# SparkX_smol_Power_AAA.net
KiCad netlist of a schematic drawn in EAGLE
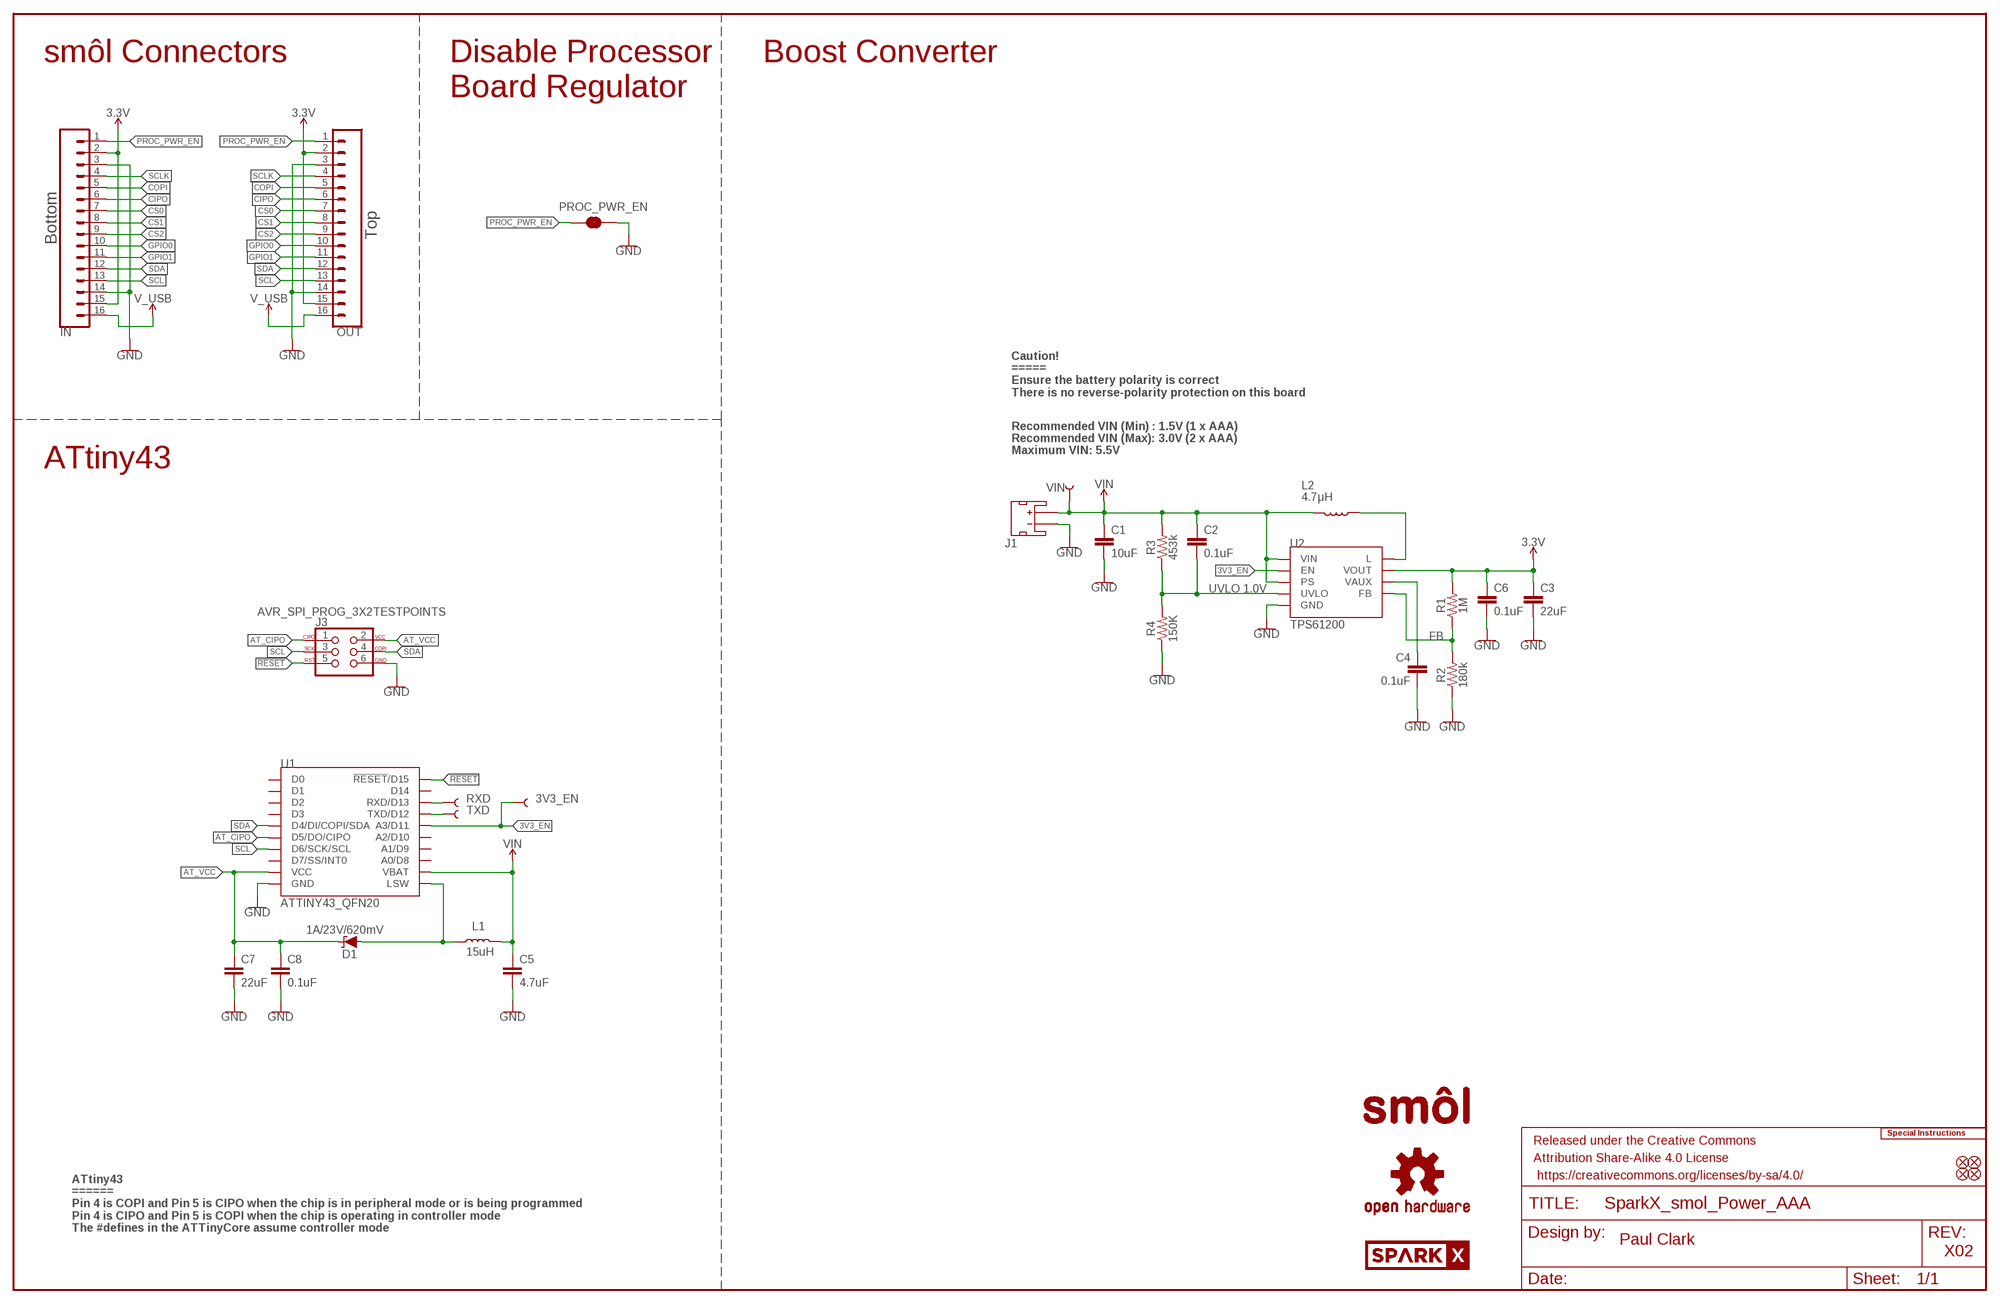
[diagram p0: schematic, sheet 1]

(export (version "E")
  (design (tool "Eeschema 10.0.6"))
  (components
    (comp (ref "3V3_EN")
      (value "TEST-POINT3X4")
      (footprint "eagle-import:PAD.03X.04")
      (libsource (lib "eagle-import") (part "TEST-POINT3X4"))
    )
    (comp (ref "C1")
      (value "10uF")
      (footprint "eagle-import:0402-TIGHT")
      (libsource (lib "eagle-import") (part "10UF-0402T-6.3V-20%"))
    )
    (comp (ref "C2")
      (value "0.1uF")
      (footprint "eagle-import:0402-TIGHT")
      (libsource (lib "eagle-import") (part "0.1UF-0402T-6.3V-10%-X7R"))
    )
    (comp (ref "C3")
      (value "22uF")
      (footprint "eagle-import:0603")
      (libsource (lib "eagle-import") (part "22UF-0603-6.3V-20%"))
    )
    (comp (ref "C4")
      (value "0.1uF")
      (footprint "eagle-import:0402-TIGHT")
      (libsource (lib "eagle-import") (part "0.1UF-0402T-6.3V-10%-X7R"))
    )
    (comp (ref "C5")
      (value "4.7uF")
      (footprint "eagle-import:0402-TIGHT")
      (libsource (lib "eagle-import") (part "4.7UF-0402_TIGHT-6.3V-20%-X5R"))
    )
    (comp (ref "C6")
      (value "0.1uF")
      (footprint "eagle-import:0402-TIGHT")
      (libsource (lib "eagle-import") (part "0.1UF-0402T-6.3V-10%-X7R"))
    )
    (comp (ref "C7")
      (value "22uF")
      (footprint "eagle-import:0603")
      (libsource (lib "eagle-import") (part "22UF-0603-6.3V-20%"))
    )
    (comp (ref "C8")
      (value "0.1uF")
      (footprint "eagle-import:0402-TIGHT")
      (libsource (lib "eagle-import") (part "0.1UF-0402T-6.3V-10%-X7R"))
    )
    (comp (ref "D1")
      (value "1A/23V/620mV")
      (footprint "eagle-import:SOD-323")
      (libsource (lib "eagle-import") (part "DIODE-SCHOTTKY-BAT20J"))
    )
    (comp (ref "FD1")
      (value "FIDUCIALUFIDUCIAL")
      (footprint "eagle-import:FIDUCIAL-MICRO")
      (libsource (lib "eagle-import") (part "FIDUCIALUFIDUCIAL"))
    )
    (comp (ref "FD2")
      (value "FIDUCIALUFIDUCIAL")
      (footprint "eagle-import:FIDUCIAL-MICRO")
      (libsource (lib "eagle-import") (part "FIDUCIALUFIDUCIAL"))
    )
    (comp (ref "FD3")
      (value "FIDUCIALUFIDUCIAL")
      (footprint "eagle-import:FIDUCIAL-MICRO")
      (libsource (lib "eagle-import") (part "FIDUCIALUFIDUCIAL"))
    )
    (comp (ref "FD4")
      (value "FIDUCIALUFIDUCIAL")
      (footprint "eagle-import:FIDUCIAL-MICRO")
      (libsource (lib "eagle-import") (part "FIDUCIALUFIDUCIAL"))
    )
    (comp (ref "FRAME1")
      (value "FRAME-LEDGER")
      (footprint "eagle-import:CREATIVE_COMMONS")
      (libsource (lib "eagle-import") (part "FRAME-LEDGER"))
    )
    (comp (ref "IN")
      (value "CONN_16FPC_16_0.5MM")
      (footprint "eagle-import:FPC_16_0.5MM")
      (libsource (lib "eagle-import") (part "CONN_16FPC_16_0.5MM"))
    )
    (comp (ref "J1")
      (value "JST_2MM_MALE")
      (footprint "eagle-import:JST-2-SMD")
      (libsource (lib "eagle-import") (part "JST_2MM_MALE"))
    )
    (comp (ref "J3")
      (value "AVR_SPI_PROG_3X2TESTPOINTS")
      (footprint "eagle-import:2X3_TEST_POINTS")
      (libsource (lib "eagle-import") (part "AVR_SPI_PROG_3X2TESTPOINTS"))
    )
    (comp (ref "L1")
      (value "15uH")
      (footprint "eagle-import:INDUCTOR_LQH32")
      (libsource (lib "eagle-import") (part "INDUCTOR-LHQ32-15UH"))
    )
    (comp (ref "L2")
      (value "4.7μH")
      (footprint "eagle-import:INDUCTOR_4X4MM")
      (libsource (lib "eagle-import") (part "4.7μH_SHIELDED_INDUCTORNPIS_LS"))
    )
    (comp (ref "LOGO1")
      (value "SPECIAL_INSTRUCTIONS-ORDERING")
      (footprint "eagle-import:ORDERING_INSTRUCTIONS")
      (libsource (lib "eagle-import") (part "SPECIAL_INSTRUCTIONS-ORDERING"))
    )
    (comp (ref "LOGO2")
      (value "OSHW-LOGOMINI")
      (footprint "eagle-import:OSHW-LOGO-MINI")
      (libsource (lib "eagle-import") (part "OSHW-LOGOMINI"))
    )
    (comp (ref "LOGO3")
      (value "OSHW-LOGOMINI")
      (footprint "eagle-import:OSHW-LOGO-MINI")
      (libsource (lib "eagle-import") (part "OSHW-LOGOMINI"))
    )
    (comp (ref "OUT")
      (value "CONN_16FPC_16_0.5MM")
      (footprint "eagle-import:FPC_16_0.5MM")
      (libsource (lib "eagle-import") (part "CONN_16FPC_16_0.5MM"))
    )
    (comp (ref "PROC_PWR_EN")
      (value "JUMPER-SMT_2_NC_TRACE_SILK")
      (footprint "eagle-import:SMT-JUMPER_2_NC_TRACE_SILK")
      (libsource (lib "eagle-import") (part "JUMPER-SMT_2_NC_TRACE_SILK"))
    )
    (comp (ref "R1")
      (value "1M")
      (footprint "eagle-import:0402-TIGHT")
      (libsource (lib "eagle-import") (part "1MOHM-0402T-1/16W-5%"))
    )
    (comp (ref "R2")
      (value "180k")
      (footprint "eagle-import:0402-TIGHT")
      (libsource (lib "eagle-import") (part "180KOHM-0402T-1/16W-1%"))
    )
    (comp (ref "R3")
      (value "453k")
      (footprint "eagle-import:0402-TIGHT")
      (libsource (lib "eagle-import") (part "453KOHM-0402T-1/16W-1%"))
    )
    (comp (ref "R4")
      (value "150K")
      (footprint "eagle-import:0402-TIGHT")
      (libsource (lib "eagle-import") (part "150KOHM-0402T-1/16W-1%"))
    )
    (comp (ref "RXD")
      (value "TEST-POINT3X4")
      (footprint "eagle-import:PAD.03X.04")
      (libsource (lib "eagle-import") (part "TEST-POINT3X4"))
    )
    (comp (ref "TXD")
      (value "TEST-POINT3X4")
      (footprint "eagle-import:PAD.03X.04")
      (libsource (lib "eagle-import") (part "TEST-POINT3X4"))
    )
    (comp (ref "U$1")
      (value "SPARKX-LOGO3")
      (footprint "eagle-import:SPARKX-SMALL")
      (libsource (lib "eagle-import") (part "SPARKX-LOGO3"))
    )
    (comp (ref "U$13")
      (value "SMOL_LOGOSMALL")
      (footprint "eagle-import:SMOL_SMALL")
      (libsource (lib "eagle-import") (part "SMOL_LOGOSMALL"))
    )
    (comp (ref "U$14")
      (value "SMOL_LOGOSMALL")
      (footprint "eagle-import:SMOL_SMALL")
      (libsource (lib "eagle-import") (part "SMOL_LOGOSMALL"))
    )
    (comp (ref "U1")
      (value "ATTINY43_QFN20")
      (footprint "eagle-import:QFN20_20M1")
      (fields (field (name "DIGIKEY_PART") "ATTINY43U-MU-ND") (field (name "MANU_PART") "ATtiny43U-MU"))
      (libsource (lib "eagle-import") (part "ATTINY43_QFN20"))
    )
    (comp (ref "U2")
      (value "TPS61200")
      (footprint "eagle-import:QFN-10_PAD")
      (libsource (lib "eagle-import") (part "TPS61200_MINIMAL"))
    )
    (comp (ref "VIN")
      (value "TEST-POINT3X4")
      (footprint "eagle-import:PAD.03X.04")
      (libsource (lib "eagle-import") (part "TEST-POINT3X4"))
    )
  )
  (nets
    (net (code "1") (name "/FB") (class "Default")
      (node (ref "R1") (pin "1") (pinfunction "1_1") (pintype "passive"))
      (node (ref "R2") (pin "2") (pinfunction "2_2") (pintype "passive"))
      (node (ref "U2") (pin "10") (pinfunction "FB_10") (pintype "passive"))
    )
    (net (code "2") (name "/~{RESET}") (class "Default")
      (node (ref "J3") (pin "5") (pinfunction "5_5") (pintype "passive"))
      (node (ref "U1") (pin "18") (pinfunction "~{RESET}/D15_18") (pintype "bidirectional"))
    )
    (net (code "3") (name "3.3V") (class "Default")
      (node (ref "C3") (pin "1") (pinfunction "1_1") (pintype "passive"))
      (node (ref "C6") (pin "1") (pinfunction "1_1") (pintype "passive"))
      (node (ref "IN") (pin "15") (pinfunction "15_15") (pintype "passive"))
      (node (ref "IN") (pin "2") (pinfunction "2_2") (pintype "passive"))
      (node (ref "OUT") (pin "15") (pinfunction "15_15") (pintype "passive"))
      (node (ref "OUT") (pin "2") (pinfunction "2_2") (pintype "passive"))
      (node (ref "R1") (pin "2") (pinfunction "2_2") (pintype "passive"))
      (node (ref "U2") (pin "2") (pinfunction "VOUT_2") (pintype "power_in"))
    )
    (net (code "4") (name "3V3_EN") (class "Default")
      (node (ref "3V3_EN") (pin "1") (pinfunction "1_1") (pintype "bidirectional"))
      (node (ref "U1") (pin "14") (pinfunction "A3/D11_14") (pintype "bidirectional"))
      (node (ref "U2") (pin "6") (pinfunction "EN_6") (pintype "input"))
    )
    (net (code "5") (name "AT_CIPO") (class "Default")
      (node (ref "J3") (pin "1") (pinfunction "1_1") (pintype "passive"))
      (node (ref "U1") (pin "4") (pinfunction "D5/DO/CIPO_4") (pintype "bidirectional"))
    )
    (net (code "6") (name "AT_VCC") (class "Default")
      (node (ref "C7") (pin "1") (pinfunction "1_1") (pintype "passive"))
      (node (ref "C8") (pin "1") (pinfunction "1_1") (pintype "passive"))
      (node (ref "D1") (pin "C") (pinfunction "C_C") (pintype "passive"))
      (node (ref "J3") (pin "2") (pinfunction "2_2") (pintype "passive"))
      (node (ref "U1") (pin "7") (pinfunction "VCC_7") (pintype "power_in"))
    )
    (net (code "7") (name "CIPO") (class "Default")
      (node (ref "IN") (pin "6") (pinfunction "6_6") (pintype "passive"))
      (node (ref "OUT") (pin "6") (pinfunction "6_6") (pintype "passive"))
    )
    (net (code "8") (name "COPI") (class "Default")
      (node (ref "IN") (pin "5") (pinfunction "5_5") (pintype "passive"))
      (node (ref "OUT") (pin "5") (pinfunction "5_5") (pintype "passive"))
    )
    (net (code "9") (name "CS0") (class "Default")
      (node (ref "IN") (pin "7") (pinfunction "7_7") (pintype "passive"))
      (node (ref "OUT") (pin "7") (pinfunction "7_7") (pintype "passive"))
    )
    (net (code "10") (name "CS1") (class "Default")
      (node (ref "IN") (pin "8") (pinfunction "8_8") (pintype "passive"))
      (node (ref "OUT") (pin "8") (pinfunction "8_8") (pintype "passive"))
    )
    (net (code "11") (name "CS2") (class "Default")
      (node (ref "IN") (pin "9") (pinfunction "9_9") (pintype "passive"))
      (node (ref "OUT") (pin "9") (pinfunction "9_9") (pintype "passive"))
    )
    (net (code "12") (name "GND") (class "Default")
      (node (ref "C1") (pin "2") (pinfunction "2_2") (pintype "passive"))
      (node (ref "C3") (pin "2") (pinfunction "2_2") (pintype "passive"))
      (node (ref "C4") (pin "2") (pinfunction "2_2") (pintype "passive"))
      (node (ref "C5") (pin "2") (pinfunction "2_2") (pintype "passive"))
      (node (ref "C6") (pin "2") (pinfunction "2_2") (pintype "passive"))
      (node (ref "C7") (pin "2") (pinfunction "2_2") (pintype "passive"))
      (node (ref "C8") (pin "2") (pinfunction "2_2") (pintype "passive"))
      (node (ref "IN") (pin "14") (pinfunction "14_14") (pintype "passive"))
      (node (ref "IN") (pin "3") (pinfunction "3_3") (pintype "passive"))
      (node (ref "J1") (pin "1") (pinfunction "-_1") (pintype "bidirectional"))
      (node (ref "J3") (pin "6") (pinfunction "6_6") (pintype "passive"))
      (node (ref "OUT") (pin "14") (pinfunction "14_14") (pintype "passive"))
      (node (ref "OUT") (pin "3") (pinfunction "3_3") (pintype "passive"))
      (node (ref "PROC_PWR_EN") (pin "2") (pinfunction "2_2") (pintype "passive"))
      (node (ref "R2") (pin "1") (pinfunction "1_1") (pintype "passive"))
      (node (ref "R4") (pin "1") (pinfunction "1_1") (pintype "passive"))
      (node (ref "U1") (pin "8") (pinfunction "GND_8") (pintype "power_in"))
      (node (ref "U1") (pin "PAD") (pinfunction "GND_PAD") (pintype "power_in"))
      (node (ref "U2") (pin "11") (pinfunction "GND_11") (pintype "power_in"))
      (node (ref "U2") (pin "12") (pinfunction "GND_12") (pintype "power_in"))
      (node (ref "U2") (pin "13") (pinfunction "GND_13") (pintype "power_in"))
      (node (ref "U2") (pin "14") (pinfunction "GND_14") (pintype "power_in"))
      (node (ref "U2") (pin "15") (pinfunction "GND_15") (pintype "power_in"))
      (node (ref "U2") (pin "4") (pinfunction "GND_4") (pintype "power_in"))
      (node (ref "U2") (pin "9") (pinfunction "GND_9") (pintype "power_in"))
    )
    (net (code "13") (name "GPIO0") (class "Default")
      (node (ref "IN") (pin "10") (pinfunction "10_10") (pintype "passive"))
      (node (ref "OUT") (pin "10") (pinfunction "10_10") (pintype "passive"))
    )
    (net (code "14") (name "GPIO1") (class "Default")
      (node (ref "IN") (pin "11") (pinfunction "11_11") (pintype "passive"))
      (node (ref "OUT") (pin "11") (pinfunction "11_11") (pintype "passive"))
    )
    (net (code "15") (name "Net-(L1-1)") (class "Default")
      (node (ref "D1") (pin "A") (pinfunction "A_A") (pintype "passive"))
      (node (ref "L1") (pin "P$1") (pinfunction "1_P$1") (pintype "passive"))
      (node (ref "U1") (pin "9") (pinfunction "LSW_9") (pintype "power_in"))
    )
    (net (code "16") (name "Net-(L2-1)") (class "Default")
      (node (ref "L2") (pin "P$1") (pinfunction "1_P$1") (pintype "passive"))
      (node (ref "U2") (pin "3") (pinfunction "L_3") (pintype "passive"))
    )
    (net (code "17") (name "Net-(U1-RXD{slash}D13)") (class "Default")
      (node (ref "RXD") (pin "1") (pinfunction "1_1") (pintype "bidirectional"))
      (node (ref "U1") (pin "16") (pinfunction "RXD/D13_16") (pintype "bidirectional"))
    )
    (net (code "18") (name "Net-(U1-TXD{slash}D12)") (class "Default")
      (node (ref "TXD") (pin "1") (pinfunction "1_1") (pintype "bidirectional"))
      (node (ref "U1") (pin "15") (pinfunction "TXD/D12_15") (pintype "bidirectional"))
    )
    (net (code "19") (name "Net-(U2-UVLO)") (class "Default")
      (node (ref "C2") (pin "2") (pinfunction "2_2") (pintype "passive"))
      (node (ref "R3") (pin "1") (pinfunction "1_1") (pintype "passive"))
      (node (ref "R4") (pin "2") (pinfunction "2_2") (pintype "passive"))
      (node (ref "U2") (pin "7") (pinfunction "UVLO_7") (pintype "input"))
    )
    (net (code "20") (name "Net-(U2-VAUX)") (class "Default")
      (node (ref "C4") (pin "1") (pinfunction "1_1") (pintype "passive"))
      (node (ref "U2") (pin "1") (pinfunction "VAUX_1") (pintype "passive"))
    )
    (net (code "21") (name "PROC_PWR_EN") (class "Default")
      (node (ref "IN") (pin "1") (pinfunction "1_1") (pintype "passive"))
      (node (ref "OUT") (pin "1") (pinfunction "1_1") (pintype "passive"))
      (node (ref "PROC_PWR_EN") (pin "1") (pinfunction "1_1") (pintype "passive"))
    )
    (net (code "22") (name "SCL") (class "Default")
      (node (ref "IN") (pin "13") (pinfunction "13_13") (pintype "passive"))
      (node (ref "J3") (pin "3") (pinfunction "3_3") (pintype "passive"))
      (node (ref "OUT") (pin "13") (pinfunction "13_13") (pintype "passive"))
      (node (ref "U1") (pin "5") (pinfunction "D6/SCK/SCL_5") (pintype "bidirectional"))
    )
    (net (code "23") (name "SCLK") (class "Default")
      (node (ref "IN") (pin "4") (pinfunction "4_4") (pintype "passive"))
      (node (ref "OUT") (pin "4") (pinfunction "4_4") (pintype "passive"))
    )
    (net (code "24") (name "SDA") (class "Default")
      (node (ref "IN") (pin "12") (pinfunction "12_12") (pintype "passive"))
      (node (ref "J3") (pin "4") (pinfunction "4_4") (pintype "passive"))
      (node (ref "OUT") (pin "12") (pinfunction "12_12") (pintype "passive"))
      (node (ref "U1") (pin "3") (pinfunction "D4/DI/COPI/SDA_3") (pintype "bidirectional"))
    )
    (net (code "25") (name "VIN") (class "Default")
      (node (ref "C1") (pin "1") (pinfunction "1_1") (pintype "passive"))
      (node (ref "C2") (pin "1") (pinfunction "1_1") (pintype "passive"))
      (node (ref "C5") (pin "1") (pinfunction "1_1") (pintype "passive"))
      (node (ref "J1") (pin "2") (pinfunction "+_2") (pintype "bidirectional"))
      (node (ref "L1") (pin "P$2") (pinfunction "2_P$2") (pintype "passive"))
      (node (ref "L2") (pin "P$2") (pinfunction "2_P$2") (pintype "passive"))
      (node (ref "R3") (pin "2") (pinfunction "2_2") (pintype "passive"))
      (node (ref "U1") (pin "10") (pinfunction "VBAT_10") (pintype "power_in"))
      (node (ref "U2") (pin "5") (pinfunction "VIN_5") (pintype "power_in"))
      (node (ref "U2") (pin "8") (pinfunction "PS_8") (pintype "input"))
      (node (ref "VIN") (pin "1") (pinfunction "1_1") (pintype "bidirectional"))
    )
    (net (code "26") (name "V_USB") (class "Default")
      (node (ref "IN") (pin "16") (pinfunction "16_16") (pintype "passive"))
      (node (ref "OUT") (pin "16") (pinfunction "16_16") (pintype "passive"))
    )
    (net (code "27") (name "unconnected-(J1-PAD1-PadNC1)") (class "Default")
      (node (ref "J1") (pin "NC1") (pinfunction "PAD1_NC1") (pintype "bidirectional"))
    )
    (net (code "28") (name "unconnected-(J1-PAD2-PadNC2)") (class "Default")
      (node (ref "J1") (pin "NC2") (pinfunction "PAD2_NC2") (pintype "bidirectional"))
    )
    (net (code "29") (name "unconnected-(U1-A0{slash}D8-Pad11)") (class "Default")
      (node (ref "U1") (pin "11") (pinfunction "A0/D8_11") (pintype "bidirectional"))
    )
    (net (code "30") (name "unconnected-(U1-A1{slash}D9-Pad12)") (class "Default")
      (node (ref "U1") (pin "12") (pinfunction "A1/D9_12") (pintype "bidirectional"))
    )
    (net (code "31") (name "unconnected-(U1-A2{slash}D10-Pad13)") (class "Default")
      (node (ref "U1") (pin "13") (pinfunction "A2/D10_13") (pintype "bidirectional"))
    )
    (net (code "32") (name "unconnected-(U1-D0-Pad19)") (class "Default")
      (node (ref "U1") (pin "19") (pinfunction "D0_19") (pintype "bidirectional"))
    )
    (net (code "33") (name "unconnected-(U1-D1-Pad20)") (class "Default")
      (node (ref "U1") (pin "20") (pinfunction "D1_20") (pintype "bidirectional"))
    )
    (net (code "34") (name "unconnected-(U1-D2-Pad1)") (class "Default")
      (node (ref "U1") (pin "1") (pinfunction "D2_1") (pintype "bidirectional"))
    )
    (net (code "35") (name "unconnected-(U1-D3-Pad2)") (class "Default")
      (node (ref "U1") (pin "2") (pinfunction "D3_2") (pintype "bidirectional"))
    )
    (net (code "36") (name "unconnected-(U1-D7{slash}SS{slash}INT0-Pad6)") (class "Default")
      (node (ref "U1") (pin "6") (pinfunction "D7/SS/INT0_6") (pintype "bidirectional"))
    )
    (net (code "37") (name "unconnected-(U1-D14-Pad17)") (class "Default")
      (node (ref "U1") (pin "17") (pinfunction "D14_17") (pintype "bidirectional"))
    )
  )
)
